# proto_base.net
KiCad netlist of a schematic drawn in EAGLE
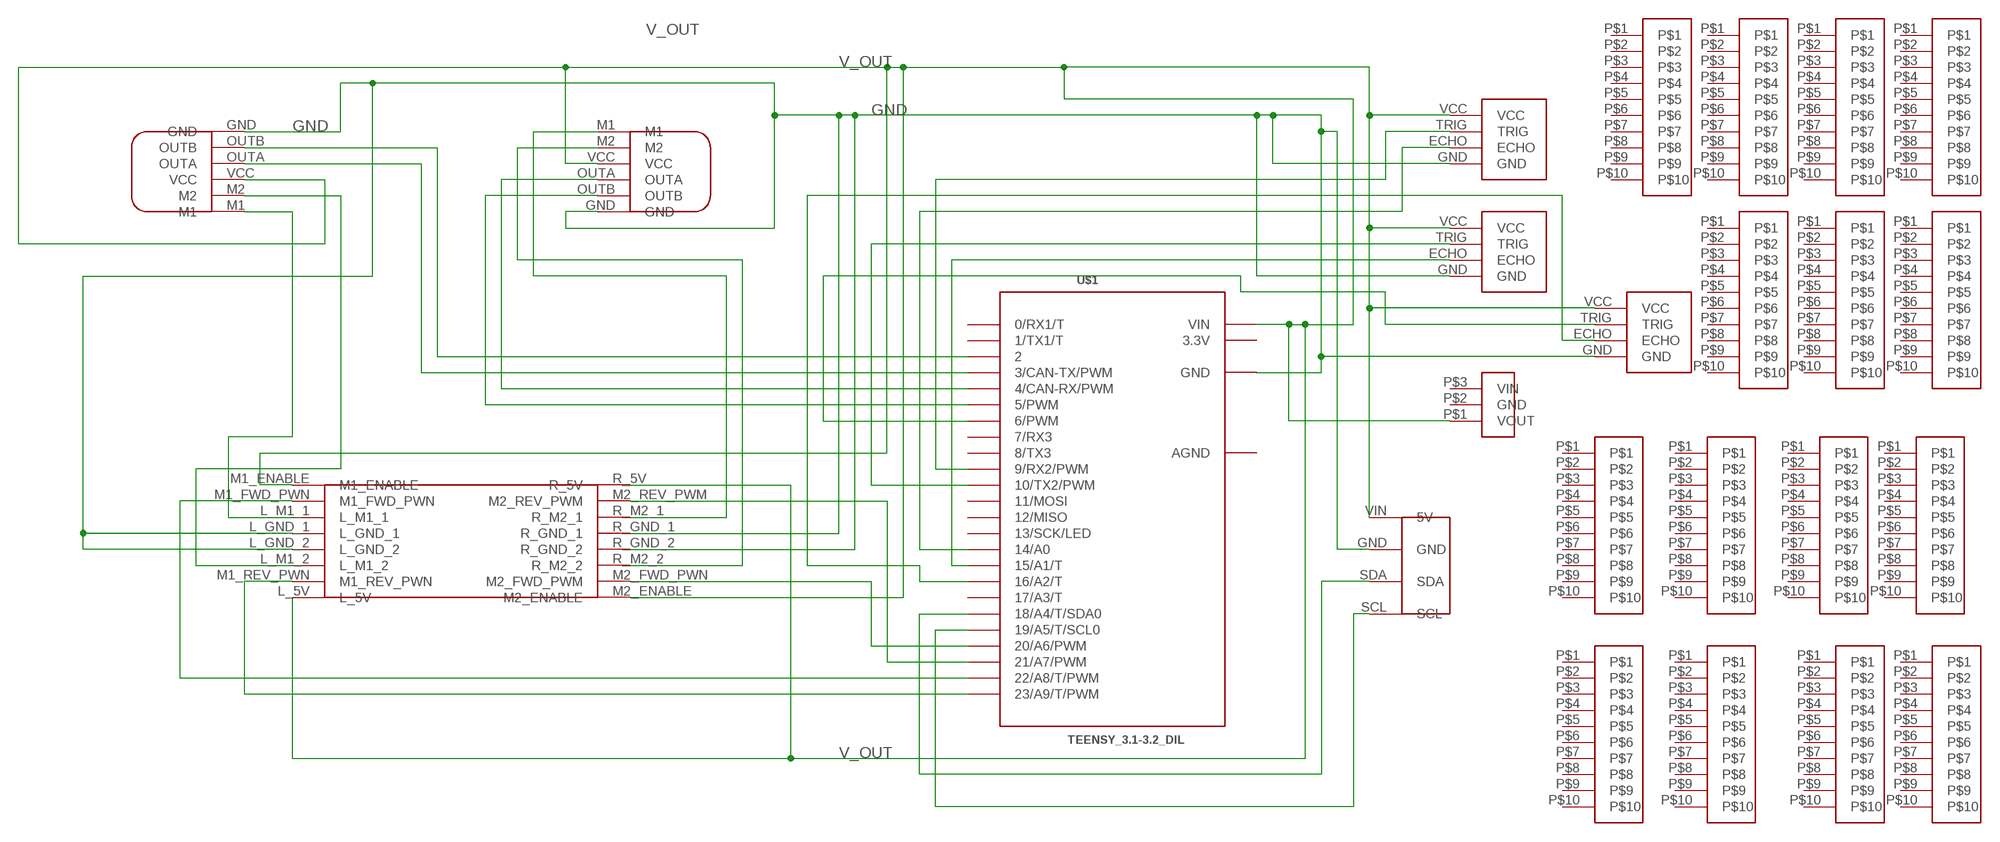
[diagram p0: schematic, sheet 1]

(export (version "E")
  (design (tool "Eeschema 10.0.6"))
  (components
    (comp (ref "IMU")
      (value "IMU")
      (footprint "eagle-import:IMU")
      (libsource (lib "eagle-import") (part "IMU"))
    )
    (comp (ref "LEFT_ENCODER")
      (value "MOTOR_ENCODER")
      (footprint "eagle-import:MOTOR_ENCODER")
      (libsource (lib "eagle-import") (part "MOTOR_ENCODER"))
    )
    (comp (ref "MOTOR_DRIVER")
      (value "MOTOR_DRIVER")
      (footprint "eagle-import:MOTOR_DRIVER")
      (libsource (lib "eagle-import") (part "MOTOR_DRIVER"))
    )
    (comp (ref "RIGHT_ENCODER")
      (value "MOTOR_ENCODER")
      (footprint "eagle-import:MOTOR_ENCODER")
      (libsource (lib "eagle-import") (part "MOTOR_ENCODER"))
    )
    (comp (ref "U$1")
      (value "TEENSY_3.1-3.2_DIL")
      (footprint "eagle-import:TEENSY_3.0-3.2&LC_DIL")
      (libsource (lib "eagle-import") (part "TEENSY_3.1-3.2_DIL"))
    )
    (comp (ref "U$2")
      (value "VOLTAGE_REGULATOR")
      (footprint "eagle-import:VOLTAGE_REGULATOR")
      (libsource (lib "eagle-import") (part "VOLTAGE_REGULATOR"))
    )
    (comp (ref "U$3")
      (value "SONAR_SENSOR")
      (footprint "eagle-import:SONAR_SENSOR")
      (libsource (lib "eagle-import") (part "SONAR_SENSOR"))
    )
    (comp (ref "U$4")
      (value "SONAR_SENSOR")
      (footprint "eagle-import:SONAR_SENSOR")
      (libsource (lib "eagle-import") (part "SONAR_SENSOR"))
    )
    (comp (ref "U$5")
      (value "SONAR_SENSOR")
      (footprint "eagle-import:SONAR_SENSOR")
      (libsource (lib "eagle-import") (part "SONAR_SENSOR"))
    )
    (comp (ref "U$6")
      (value "TEST_ROW")
      (footprint "eagle-import:TEST_ROW")
      (libsource (lib "eagle-import") (part "TEST_ROW"))
    )
    (comp (ref "U$7")
      (value "TEST_ROW")
      (footprint "eagle-import:TEST_ROW")
      (libsource (lib "eagle-import") (part "TEST_ROW"))
    )
    (comp (ref "U$8")
      (value "TEST_ROW")
      (footprint "eagle-import:TEST_ROW")
      (libsource (lib "eagle-import") (part "TEST_ROW"))
    )
    (comp (ref "U$9")
      (value "TEST_ROW")
      (footprint "eagle-import:TEST_ROW")
      (libsource (lib "eagle-import") (part "TEST_ROW"))
    )
    (comp (ref "U$10")
      (value "TEST_ROW")
      (footprint "eagle-import:TEST_ROW")
      (libsource (lib "eagle-import") (part "TEST_ROW"))
    )
    (comp (ref "U$11")
      (value "TEST_ROW")
      (footprint "eagle-import:TEST_ROW")
      (libsource (lib "eagle-import") (part "TEST_ROW"))
    )
    (comp (ref "U$12")
      (value "TEST_ROW")
      (footprint "eagle-import:TEST_ROW")
      (libsource (lib "eagle-import") (part "TEST_ROW"))
    )
    (comp (ref "U$13")
      (value "TEST_ROW")
      (footprint "eagle-import:TEST_ROW")
      (libsource (lib "eagle-import") (part "TEST_ROW"))
    )
    (comp (ref "U$14")
      (value "TEST_ROW")
      (footprint "eagle-import:TEST_ROW")
      (libsource (lib "eagle-import") (part "TEST_ROW"))
    )
    (comp (ref "U$15")
      (value "TEST_ROW")
      (footprint "eagle-import:TEST_ROW")
      (libsource (lib "eagle-import") (part "TEST_ROW"))
    )
    (comp (ref "U$16")
      (value "TEST_ROW")
      (footprint "eagle-import:TEST_ROW")
      (libsource (lib "eagle-import") (part "TEST_ROW"))
    )
    (comp (ref "U$17")
      (value "TEST_ROW")
      (footprint "eagle-import:TEST_ROW")
      (libsource (lib "eagle-import") (part "TEST_ROW"))
    )
    (comp (ref "U$18")
      (value "TEST_ROW")
      (footprint "eagle-import:TEST_ROW")
      (libsource (lib "eagle-import") (part "TEST_ROW"))
    )
    (comp (ref "U$19")
      (value "TEST_ROW")
      (footprint "eagle-import:TEST_ROW")
      (libsource (lib "eagle-import") (part "TEST_ROW"))
    )
    (comp (ref "U$20")
      (value "TEST_ROW")
      (footprint "eagle-import:TEST_ROW")
      (libsource (lib "eagle-import") (part "TEST_ROW"))
    )
  )
  (nets
    (net (code "1") (name "/3.3V") (class "Default")
      (node (ref "U$1") (pin "3.3V") (pinfunction "3.3V_3.3V") (pintype "power_in"))
    )
    (net (code "2") (name "/AGND") (class "Default")
      (node (ref "U$1") (pin "AGND") (pinfunction "AGND_AGND") (pintype "power_in"))
    )
    (net (code "3") (name "/GND") (class "Default")
      (node (ref "IMU") (pin "GND") (pinfunction "GND_GND") (pintype "bidirectional"))
      (node (ref "LEFT_ENCODER") (pin "GND") (pinfunction "GND_GND") (pintype "bidirectional"))
      (node (ref "MOTOR_DRIVER") (pin "L_GND_1") (pinfunction "L_GND_1_L_GND_1") (pintype "bidirectional"))
      (node (ref "MOTOR_DRIVER") (pin "L_GND_2") (pinfunction "L_GND_2_L_GND_2") (pintype "bidirectional"))
      (node (ref "MOTOR_DRIVER") (pin "R_GND_1") (pinfunction "R_GND_1_R_GND_1") (pintype "bidirectional"))
      (node (ref "MOTOR_DRIVER") (pin "R_GND_2") (pinfunction "R_GND_2_R_GND_2") (pintype "bidirectional"))
      (node (ref "RIGHT_ENCODER") (pin "GND") (pinfunction "GND_GND") (pintype "bidirectional"))
      (node (ref "U$1") (pin "GND") (pinfunction "GND_GND") (pintype "power_in"))
      (node (ref "U$3") (pin "GND") (pinfunction "GND_GND") (pintype "bidirectional"))
      (node (ref "U$4") (pin "GND") (pinfunction "GND_GND") (pintype "bidirectional"))
      (node (ref "U$5") (pin "GND") (pinfunction "GND_GND") (pintype "bidirectional"))
    )
    (net (code "4") (name "/V_OUT") (class "Default")
      (node (ref "IMU") (pin "VIN") (pinfunction "5V_VIN") (pintype "bidirectional"))
      (node (ref "LEFT_ENCODER") (pin "VCC") (pinfunction "VCC_VCC") (pintype "bidirectional"))
      (node (ref "MOTOR_DRIVER") (pin "L_5V") (pinfunction "L_5V_L_5V") (pintype "bidirectional"))
      (node (ref "MOTOR_DRIVER") (pin "M1_ENABLE") (pinfunction "M1_ENABLE_M1_ENABLE") (pintype "bidirectional"))
      (node (ref "MOTOR_DRIVER") (pin "M2_ENABLE") (pinfunction "M2_ENABLE_M2_ENABLE") (pintype "bidirectional"))
      (node (ref "MOTOR_DRIVER") (pin "R_5V") (pinfunction "R_5V_R_5V") (pintype "bidirectional"))
      (node (ref "RIGHT_ENCODER") (pin "VCC") (pinfunction "VCC_VCC") (pintype "bidirectional"))
      (node (ref "U$1") (pin "VIN") (pinfunction "VIN_VIN") (pintype "power_in"))
      (node (ref "U$2") (pin "P$1") (pinfunction "VOUT_P$1") (pintype "bidirectional"))
      (node (ref "U$3") (pin "VCC") (pinfunction "VCC_VCC") (pintype "bidirectional"))
      (node (ref "U$4") (pin "VCC") (pinfunction "VCC_VCC") (pintype "bidirectional"))
      (node (ref "U$5") (pin "VCC") (pinfunction "VCC_VCC") (pintype "bidirectional"))
    )
    (net (code "5") (name "Net-(LEFT_ENCODER-PadM1)") (class "Default")
      (node (ref "LEFT_ENCODER") (pin "M1") (pinfunction "M1_M1") (pintype "bidirectional"))
      (node (ref "MOTOR_DRIVER") (pin "L_M1_1") (pinfunction "L_M1_1_L_M1_1") (pintype "bidirectional"))
    )
    (net (code "6") (name "Net-(LEFT_ENCODER-PadM2)") (class "Default")
      (node (ref "LEFT_ENCODER") (pin "M2") (pinfunction "M2_M2") (pintype "bidirectional"))
      (node (ref "MOTOR_DRIVER") (pin "L_M1_2") (pinfunction "L_M1_2_L_M1_2") (pintype "bidirectional"))
    )
    (net (code "7") (name "Net-(LEFT_ENCODER-PadOUTB)") (class "Default")
      (node (ref "LEFT_ENCODER") (pin "OUTB") (pinfunction "OUTB_OUTB") (pintype "bidirectional"))
      (node (ref "U$1") (pin "2") (pinfunction "2_2") (pintype "bidirectional"))
    )
    (net (code "8") (name "Net-(MOTOR_DRIVER-M2_FWD_PWM)") (class "Default")
      (node (ref "MOTOR_DRIVER") (pin "M2_FWD_PWN") (pinfunction "M2_FWD_PWM_M2_FWD_PWN") (pintype "bidirectional"))
      (node (ref "U$1") (pin "20/A6") (pinfunction "20/A6/PWM_20/A6") (pintype "bidirectional"))
    )
    (net (code "9") (name "Net-(MOTOR_DRIVER-PadR_M2_1)") (class "Default")
      (node (ref "MOTOR_DRIVER") (pin "R_M2_1") (pinfunction "R_M2_1_R_M2_1") (pintype "bidirectional"))
      (node (ref "RIGHT_ENCODER") (pin "M1") (pinfunction "M1_M1") (pintype "bidirectional"))
    )
    (net (code "10") (name "Net-(MOTOR_DRIVER-PadR_M2_2)") (class "Default")
      (node (ref "MOTOR_DRIVER") (pin "R_M2_2") (pinfunction "R_M2_2_R_M2_2") (pintype "bidirectional"))
      (node (ref "RIGHT_ENCODER") (pin "M2") (pinfunction "M2_M2") (pintype "bidirectional"))
    )
    (net (code "11") (name "Net-(U$1-3{slash}CAN-TX{slash}PWM)") (class "Default")
      (node (ref "LEFT_ENCODER") (pin "OUTA") (pinfunction "OUTA_OUTA") (pintype "bidirectional"))
      (node (ref "U$1") (pin "3") (pinfunction "3/CAN-TX/PWM_3") (pintype "bidirectional"))
    )
    (net (code "12") (name "Net-(U$1-4{slash}CAN-RX{slash}PWM)") (class "Default")
      (node (ref "RIGHT_ENCODER") (pin "OUTA") (pinfunction "OUTA_OUTA") (pintype "bidirectional"))
      (node (ref "U$1") (pin "4") (pinfunction "4/CAN-RX/PWM_4") (pintype "bidirectional"))
    )
    (net (code "13") (name "Net-(U$1-5{slash}PWM)") (class "Default")
      (node (ref "RIGHT_ENCODER") (pin "OUTB") (pinfunction "OUTB_OUTB") (pintype "bidirectional"))
      (node (ref "U$1") (pin "5") (pinfunction "5/PWM_5") (pintype "bidirectional"))
    )
    (net (code "14") (name "Net-(U$1-6{slash}PWM)") (class "Default")
      (node (ref "U$1") (pin "6") (pinfunction "6/PWM_6") (pintype "bidirectional"))
      (node (ref "U$5") (pin "TRIG") (pinfunction "TRIG_TRIG") (pintype "bidirectional"))
    )
    (net (code "15") (name "Net-(U$1-9{slash}RX2{slash}PWM)") (class "Default")
      (node (ref "U$1") (pin "9") (pinfunction "9/RX2/PWM_9") (pintype "bidirectional"))
      (node (ref "U$3") (pin "TRIG") (pinfunction "TRIG_TRIG") (pintype "bidirectional"))
    )
    (net (code "16") (name "Net-(U$1-10{slash}TX2{slash}PWM)") (class "Default")
      (node (ref "U$1") (pin "10") (pinfunction "10/TX2/PWM_10") (pintype "bidirectional"))
      (node (ref "U$4") (pin "TRIG") (pinfunction "TRIG_TRIG") (pintype "bidirectional"))
    )
    (net (code "17") (name "Net-(U$1-15{slash}A1{slash}T)") (class "Default")
      (node (ref "U$1") (pin "15/A1") (pinfunction "15/A1/T_15/A1") (pintype "bidirectional"))
      (node (ref "U$4") (pin "ECHO") (pinfunction "ECHO_ECHO") (pintype "bidirectional"))
    )
    (net (code "18") (name "Net-(U$1-16{slash}A2{slash}T)") (class "Default")
      (node (ref "U$1") (pin "16/A2") (pinfunction "16/A2/T_16/A2") (pintype "bidirectional"))
      (node (ref "U$5") (pin "ECHO") (pinfunction "ECHO_ECHO") (pintype "bidirectional"))
    )
    (net (code "19") (name "Net-(U$1-18{slash}A4{slash}T{slash}SDA0)") (class "Default")
      (node (ref "IMU") (pin "SDA") (pinfunction "SDA_SDA") (pintype "bidirectional"))
      (node (ref "U$1") (pin "18/A4") (pinfunction "18/A4/T/SDA0_18/A4") (pintype "bidirectional"))
    )
    (net (code "20") (name "Net-(U$1-19{slash}A5{slash}T{slash}SCL0)") (class "Default")
      (node (ref "IMU") (pin "SCL") (pinfunction "SCL_SCL") (pintype "bidirectional"))
      (node (ref "U$1") (pin "19/A5") (pinfunction "19/A5/T/SCL0_19/A5") (pintype "bidirectional"))
    )
    (net (code "21") (name "Net-(U$1-21{slash}A7{slash}PWM)") (class "Default")
      (node (ref "MOTOR_DRIVER") (pin "M2_REV_PWM") (pinfunction "M2_REV_PWM_M2_REV_PWM") (pintype "bidirectional"))
      (node (ref "U$1") (pin "21/A7") (pinfunction "21/A7/PWM_21/A7") (pintype "bidirectional"))
    )
    (net (code "22") (name "Net-(U$1-22{slash}A8{slash}T{slash}PWM)") (class "Default")
      (node (ref "MOTOR_DRIVER") (pin "M1_FWD_PWN") (pinfunction "M1_FWD_PWN_M1_FWD_PWN") (pintype "bidirectional"))
      (node (ref "U$1") (pin "22/A8") (pinfunction "22/A8/T/PWM_22/A8") (pintype "bidirectional"))
    )
    (net (code "23") (name "Net-(U$1-23{slash}A9{slash}T{slash}PWM)") (class "Default")
      (node (ref "MOTOR_DRIVER") (pin "M1_REV_PWN") (pinfunction "M1_REV_PWN_M1_REV_PWN") (pintype "bidirectional"))
      (node (ref "U$1") (pin "23/A9") (pinfunction "23/A9/T/PWM_23/A9") (pintype "bidirectional"))
    )
    (net (code "24") (name "Net-(U$1-Pad14{slash}A0)") (class "Default")
      (node (ref "U$1") (pin "14/A0") (pinfunction "14/A0_14/A0") (pintype "bidirectional"))
      (node (ref "U$3") (pin "ECHO") (pinfunction "ECHO_ECHO") (pintype "bidirectional"))
    )
    (net (code "25") (name "unconnected-(U$1-0{slash}RX1{slash}T-Pad0)") (class "Default")
      (node (ref "U$1") (pin "0") (pinfunction "0/RX1/T_0") (pintype "bidirectional"))
    )
    (net (code "26") (name "unconnected-(U$1-1{slash}TX1{slash}T-Pad1)") (class "Default")
      (node (ref "U$1") (pin "1") (pinfunction "1/TX1/T_1") (pintype "bidirectional"))
    )
    (net (code "27") (name "unconnected-(U$1-7{slash}RX3-Pad7)") (class "Default")
      (node (ref "U$1") (pin "7") (pinfunction "7/RX3_7") (pintype "bidirectional"))
    )
    (net (code "28") (name "unconnected-(U$1-8{slash}TX3-Pad8)") (class "Default")
      (node (ref "U$1") (pin "8") (pinfunction "8/TX3_8") (pintype "bidirectional"))
    )
    (net (code "29") (name "unconnected-(U$1-11{slash}MOSI-Pad11)") (class "Default")
      (node (ref "U$1") (pin "11") (pinfunction "11/MOSI_11") (pintype "bidirectional"))
    )
    (net (code "30") (name "unconnected-(U$1-12{slash}MISO-Pad12)") (class "Default")
      (node (ref "U$1") (pin "12") (pinfunction "12/MISO_12") (pintype "bidirectional"))
    )
    (net (code "31") (name "unconnected-(U$1-13{slash}SCK{slash}LED-Pad13)") (class "Default")
      (node (ref "U$1") (pin "13") (pinfunction "13/SCK/LED_13") (pintype "bidirectional"))
    )
    (net (code "32") (name "unconnected-(U$1-17{slash}A3{slash}T-Pad17{slash}A3)") (class "Default")
      (node (ref "U$1") (pin "17/A3") (pinfunction "17/A3/T_17/A3") (pintype "bidirectional"))
    )
    (net (code "33") (name "unconnected-(U$2-GND-PadP$2)") (class "Default")
      (node (ref "U$2") (pin "P$2") (pinfunction "GND_P$2") (pintype "bidirectional"))
    )
    (net (code "34") (name "unconnected-(U$2-VIN-PadP$3)") (class "Default")
      (node (ref "U$2") (pin "P$3") (pinfunction "VIN_P$3") (pintype "bidirectional"))
    )
    (net (code "35") (name "unconnected-(U$6-PadP$1)") (class "Default")
      (node (ref "U$6") (pin "P$1") (pinfunction "P$1_P$1") (pintype "bidirectional"))
    )
    (net (code "36") (name "unconnected-(U$6-PadP$2)") (class "Default")
      (node (ref "U$6") (pin "P$2") (pinfunction "P$2_P$2") (pintype "bidirectional"))
    )
    (net (code "37") (name "unconnected-(U$6-PadP$3)") (class "Default")
      (node (ref "U$6") (pin "P$3") (pinfunction "P$3_P$3") (pintype "bidirectional"))
    )
    (net (code "38") (name "unconnected-(U$6-PadP$4)") (class "Default")
      (node (ref "U$6") (pin "P$4") (pinfunction "P$4_P$4") (pintype "bidirectional"))
    )
    (net (code "39") (name "unconnected-(U$6-PadP$5)") (class "Default")
      (node (ref "U$6") (pin "P$5") (pinfunction "P$5_P$5") (pintype "bidirectional"))
    )
    (net (code "40") (name "unconnected-(U$6-PadP$6)") (class "Default")
      (node (ref "U$6") (pin "P$6") (pinfunction "P$6_P$6") (pintype "bidirectional"))
    )
    (net (code "41") (name "unconnected-(U$6-PadP$7)") (class "Default")
      (node (ref "U$6") (pin "P$7") (pinfunction "P$7_P$7") (pintype "bidirectional"))
    )
    (net (code "42") (name "unconnected-(U$6-PadP$8)") (class "Default")
      (node (ref "U$6") (pin "P$8") (pinfunction "P$8_P$8") (pintype "bidirectional"))
    )
    (net (code "43") (name "unconnected-(U$6-PadP$9)") (class "Default")
      (node (ref "U$6") (pin "P$9") (pinfunction "P$9_P$9") (pintype "bidirectional"))
    )
    (net (code "44") (name "unconnected-(U$6-PadP$10)") (class "Default")
      (node (ref "U$6") (pin "P$10") (pinfunction "P$10_P$10") (pintype "bidirectional"))
    )
    (net (code "45") (name "unconnected-(U$7-PadP$1)") (class "Default")
      (node (ref "U$7") (pin "P$1") (pinfunction "P$1_P$1") (pintype "bidirectional"))
    )
    (net (code "46") (name "unconnected-(U$7-PadP$2)") (class "Default")
      (node (ref "U$7") (pin "P$2") (pinfunction "P$2_P$2") (pintype "bidirectional"))
    )
    (net (code "47") (name "unconnected-(U$7-PadP$3)") (class "Default")
      (node (ref "U$7") (pin "P$3") (pinfunction "P$3_P$3") (pintype "bidirectional"))
    )
    (net (code "48") (name "unconnected-(U$7-PadP$4)") (class "Default")
      (node (ref "U$7") (pin "P$4") (pinfunction "P$4_P$4") (pintype "bidirectional"))
    )
    (net (code "49") (name "unconnected-(U$7-PadP$5)") (class "Default")
      (node (ref "U$7") (pin "P$5") (pinfunction "P$5_P$5") (pintype "bidirectional"))
    )
    (net (code "50") (name "unconnected-(U$7-PadP$6)") (class "Default")
      (node (ref "U$7") (pin "P$6") (pinfunction "P$6_P$6") (pintype "bidirectional"))
    )
    (net (code "51") (name "unconnected-(U$7-PadP$7)") (class "Default")
      (node (ref "U$7") (pin "P$7") (pinfunction "P$7_P$7") (pintype "bidirectional"))
    )
    (net (code "52") (name "unconnected-(U$7-PadP$8)") (class "Default")
      (node (ref "U$7") (pin "P$8") (pinfunction "P$8_P$8") (pintype "bidirectional"))
    )
    (net (code "53") (name "unconnected-(U$7-PadP$9)") (class "Default")
      (node (ref "U$7") (pin "P$9") (pinfunction "P$9_P$9") (pintype "bidirectional"))
    )
    (net (code "54") (name "unconnected-(U$7-PadP$10)") (class "Default")
      (node (ref "U$7") (pin "P$10") (pinfunction "P$10_P$10") (pintype "bidirectional"))
    )
    (net (code "55") (name "unconnected-(U$8-PadP$1)") (class "Default")
      (node (ref "U$8") (pin "P$1") (pinfunction "P$1_P$1") (pintype "bidirectional"))
    )
    (net (code "56") (name "unconnected-(U$8-PadP$2)") (class "Default")
      (node (ref "U$8") (pin "P$2") (pinfunction "P$2_P$2") (pintype "bidirectional"))
    )
    (net (code "57") (name "unconnected-(U$8-PadP$3)") (class "Default")
      (node (ref "U$8") (pin "P$3") (pinfunction "P$3_P$3") (pintype "bidirectional"))
    )
    (net (code "58") (name "unconnected-(U$8-PadP$4)") (class "Default")
      (node (ref "U$8") (pin "P$4") (pinfunction "P$4_P$4") (pintype "bidirectional"))
    )
    (net (code "59") (name "unconnected-(U$8-PadP$5)") (class "Default")
      (node (ref "U$8") (pin "P$5") (pinfunction "P$5_P$5") (pintype "bidirectional"))
    )
    (net (code "60") (name "unconnected-(U$8-PadP$6)") (class "Default")
      (node (ref "U$8") (pin "P$6") (pinfunction "P$6_P$6") (pintype "bidirectional"))
    )
    (net (code "61") (name "unconnected-(U$8-PadP$7)") (class "Default")
      (node (ref "U$8") (pin "P$7") (pinfunction "P$7_P$7") (pintype "bidirectional"))
    )
    (net (code "62") (name "unconnected-(U$8-PadP$8)") (class "Default")
      (node (ref "U$8") (pin "P$8") (pinfunction "P$8_P$8") (pintype "bidirectional"))
    )
    (net (code "63") (name "unconnected-(U$8-PadP$9)") (class "Default")
      (node (ref "U$8") (pin "P$9") (pinfunction "P$9_P$9") (pintype "bidirectional"))
    )
    (net (code "64") (name "unconnected-(U$8-PadP$10)") (class "Default")
      (node (ref "U$8") (pin "P$10") (pinfunction "P$10_P$10") (pintype "bidirectional"))
    )
    (net (code "65") (name "unconnected-(U$9-PadP$1)") (class "Default")
      (node (ref "U$9") (pin "P$1") (pinfunction "P$1_P$1") (pintype "bidirectional"))
    )
    (net (code "66") (name "unconnected-(U$9-PadP$2)") (class "Default")
      (node (ref "U$9") (pin "P$2") (pinfunction "P$2_P$2") (pintype "bidirectional"))
    )
    (net (code "67") (name "unconnected-(U$9-PadP$3)") (class "Default")
      (node (ref "U$9") (pin "P$3") (pinfunction "P$3_P$3") (pintype "bidirectional"))
    )
    (net (code "68") (name "unconnected-(U$9-PadP$4)") (class "Default")
      (node (ref "U$9") (pin "P$4") (pinfunction "P$4_P$4") (pintype "bidirectional"))
    )
    (net (code "69") (name "unconnected-(U$9-PadP$5)") (class "Default")
      (node (ref "U$9") (pin "P$5") (pinfunction "P$5_P$5") (pintype "bidirectional"))
    )
    (net (code "70") (name "unconnected-(U$9-PadP$6)") (class "Default")
      (node (ref "U$9") (pin "P$6") (pinfunction "P$6_P$6") (pintype "bidirectional"))
    )
    (net (code "71") (name "unconnected-(U$9-PadP$7)") (class "Default")
      (node (ref "U$9") (pin "P$7") (pinfunction "P$7_P$7") (pintype "bidirectional"))
    )
    (net (code "72") (name "unconnected-(U$9-PadP$8)") (class "Default")
      (node (ref "U$9") (pin "P$8") (pinfunction "P$8_P$8") (pintype "bidirectional"))
    )
    (net (code "73") (name "unconnected-(U$9-PadP$9)") (class "Default")
      (node (ref "U$9") (pin "P$9") (pinfunction "P$9_P$9") (pintype "bidirectional"))
    )
    (net (code "74") (name "unconnected-(U$9-PadP$10)") (class "Default")
      (node (ref "U$9") (pin "P$10") (pinfunction "P$10_P$10") (pintype "bidirectional"))
    )
    (net (code "75") (name "unconnected-(U$10-PadP$1)") (class "Default")
      (node (ref "U$10") (pin "P$1") (pinfunction "P$1_P$1") (pintype "bidirectional"))
    )
    (net (code "76") (name "unconnected-(U$10-PadP$2)") (class "Default")
      (node (ref "U$10") (pin "P$2") (pinfunction "P$2_P$2") (pintype "bidirectional"))
    )
    (net (code "77") (name "unconnected-(U$10-PadP$3)") (class "Default")
      (node (ref "U$10") (pin "P$3") (pinfunction "P$3_P$3") (pintype "bidirectional"))
    )
    (net (code "78") (name "unconnected-(U$10-PadP$4)") (class "Default")
      (node (ref "U$10") (pin "P$4") (pinfunction "P$4_P$4") (pintype "bidirectional"))
    )
    (net (code "79") (name "unconnected-(U$10-PadP$5)") (class "Default")
      (node (ref "U$10") (pin "P$5") (pinfunction "P$5_P$5") (pintype "bidirectional"))
    )
    (net (code "80") (name "unconnected-(U$10-PadP$6)") (class "Default")
      (node (ref "U$10") (pin "P$6") (pinfunction "P$6_P$6") (pintype "bidirectional"))
    )
    (net (code "81") (name "unconnected-(U$10-PadP$7)") (class "Default")
      (node (ref "U$10") (pin "P$7") (pinfunction "P$7_P$7") (pintype "bidirectional"))
    )
    (net (code "82") (name "unconnected-(U$10-PadP$8)") (class "Default")
      (node (ref "U$10") (pin "P$8") (pinfunction "P$8_P$8") (pintype "bidirectional"))
    )
    (net (code "83") (name "unconnected-(U$10-PadP$9)") (class "Default")
      (node (ref "U$10") (pin "P$9") (pinfunction "P$9_P$9") (pintype "bidirectional"))
    )
    (net (code "84") (name "unconnected-(U$10-PadP$10)") (class "Default")
      (node (ref "U$10") (pin "P$10") (pinfunction "P$10_P$10") (pintype "bidirectional"))
    )
    (net (code "85") (name "unconnected-(U$11-PadP$1)") (class "Default")
      (node (ref "U$11") (pin "P$1") (pinfunction "P$1_P$1") (pintype "bidirectional"))
    )
    (net (code "86") (name "unconnected-(U$11-PadP$2)") (class "Default")
      (node (ref "U$11") (pin "P$2") (pinfunction "P$2_P$2") (pintype "bidirectional"))
    )
    (net (code "87") (name "unconnected-(U$11-PadP$3)") (class "Default")
      (node (ref "U$11") (pin "P$3") (pinfunction "P$3_P$3") (pintype "bidirectional"))
    )
    (net (code "88") (name "unconnected-(U$11-PadP$4)") (class "Default")
      (node (ref "U$11") (pin "P$4") (pinfunction "P$4_P$4") (pintype "bidirectional"))
    )
    (net (code "89") (name "unconnected-(U$11-PadP$5)") (class "Default")
      (node (ref "U$11") (pin "P$5") (pinfunction "P$5_P$5") (pintype "bidirectional"))
    )
    (net (code "90") (name "unconnected-(U$11-PadP$6)") (class "Default")
      (node (ref "U$11") (pin "P$6") (pinfunction "P$6_P$6") (pintype "bidirectional"))
    )
    (net (code "91") (name "unconnected-(U$11-PadP$7)") (class "Default")
      (node (ref "U$11") (pin "P$7") (pinfunction "P$7_P$7") (pintype "bidirectional"))
    )
    (net (code "92") (name "unconnected-(U$11-PadP$8)") (class "Default")
      (node (ref "U$11") (pin "P$8") (pinfunction "P$8_P$8") (pintype "bidirectional"))
    )
    (net (code "93") (name "unconnected-(U$11-PadP$9)") (class "Default")
      (node (ref "U$11") (pin "P$9") (pinfunction "P$9_P$9") (pintype "bidirectional"))
    )
    (net (code "94") (name "unconnected-(U$11-PadP$10)") (class "Default")
      (node (ref "U$11") (pin "P$10") (pinfunction "P$10_P$10") (pintype "bidirectional"))
    )
    (net (code "95") (name "unconnected-(U$12-PadP$1)") (class "Default")
      (node (ref "U$12") (pin "P$1") (pinfunction "P$1_P$1") (pintype "bidirectional"))
    )
    (net (code "96") (name "unconnected-(U$12-PadP$2)") (class "Default")
      (node (ref "U$12") (pin "P$2") (pinfunction "P$2_P$2") (pintype "bidirectional"))
    )
    (net (code "97") (name "unconnected-(U$12-PadP$3)") (class "Default")
      (node (ref "U$12") (pin "P$3") (pinfunction "P$3_P$3") (pintype "bidirectional"))
    )
    (net (code "98") (name "unconnected-(U$12-PadP$4)") (class "Default")
      (node (ref "U$12") (pin "P$4") (pinfunction "P$4_P$4") (pintype "bidirectional"))
    )
    (net (code "99") (name "unconnected-(U$12-PadP$5)") (class "Default")
      (node (ref "U$12") (pin "P$5") (pinfunction "P$5_P$5") (pintype "bidirectional"))
    )
    (net (code "100") (name "unconnected-(U$12-PadP$6)") (class "Default")
      (node (ref "U$12") (pin "P$6") (pinfunction "P$6_P$6") (pintype "bidirectional"))
    )
    (net (code "101") (name "unconnected-(U$12-PadP$7)") (class "Default")
      (node (ref "U$12") (pin "P$7") (pinfunction "P$7_P$7") (pintype "bidirectional"))
    )
    (net (code "102") (name "unconnected-(U$12-PadP$8)") (class "Default")
      (node (ref "U$12") (pin "P$8") (pinfunction "P$8_P$8") (pintype "bidirectional"))
    )
    (net (code "103") (name "unconnected-(U$12-PadP$9)") (class "Default")
      (node (ref "U$12") (pin "P$9") (pinfunction "P$9_P$9") (pintype "bidirectional"))
    )
    (net (code "104") (name "unconnected-(U$12-PadP$10)") (class "Default")
      (node (ref "U$12") (pin "P$10") (pinfunction "P$10_P$10") (pintype "bidirectional"))
    )
    (net (code "105") (name "unconnected-(U$13-PadP$1)") (class "Default")
      (node (ref "U$13") (pin "P$1") (pinfunction "P$1_P$1") (pintype "bidirectional"))
    )
    (net (code "106") (name "unconnected-(U$13-PadP$2)") (class "Default")
      (node (ref "U$13") (pin "P$2") (pinfunction "P$2_P$2") (pintype "bidirectional"))
    )
    (net (code "107") (name "unconnected-(U$13-PadP$3)") (class "Default")
      (node (ref "U$13") (pin "P$3") (pinfunction "P$3_P$3") (pintype "bidirectional"))
    )
    (net (code "108") (name "unconnected-(U$13-PadP$4)") (class "Default")
      (node (ref "U$13") (pin "P$4") (pinfunction "P$4_P$4") (pintype "bidirectional"))
    )
    (net (code "109") (name "unconnected-(U$13-PadP$5)") (class "Default")
      (node (ref "U$13") (pin "P$5") (pinfunction "P$5_P$5") (pintype "bidirectional"))
    )
    (net (code "110") (name "unconnected-(U$13-PadP$6)") (class "Default")
      (node (ref "U$13") (pin "P$6") (pinfunction "P$6_P$6") (pintype "bidirectional"))
    )
    (net (code "111") (name "unconnected-(U$13-PadP$7)") (class "Default")
      (node (ref "U$13") (pin "P$7") (pinfunction "P$7_P$7") (pintype "bidirectional"))
    )
    (net (code "112") (name "unconnected-(U$13-PadP$8)") (class "Default")
      (node (ref "U$13") (pin "P$8") (pinfunction "P$8_P$8") (pintype "bidirectional"))
    )
    (net (code "113") (name "unconnected-(U$13-PadP$9)") (class "Default")
      (node (ref "U$13") (pin "P$9") (pinfunction "P$9_P$9") (pintype "bidirectional"))
    )
    (net (code "114") (name "unconnected-(U$13-PadP$10)") (class "Default")
      (node (ref "U$13") (pin "P$10") (pinfunction "P$10_P$10") (pintype "bidirectional"))
    )
    (net (code "115") (name "unconnected-(U$14-PadP$1)") (class "Default")
      (node (ref "U$14") (pin "P$1") (pinfunction "P$1_P$1") (pintype "bidirectional"))
    )
    (net (code "116") (name "unconnected-(U$14-PadP$2)") (class "Default")
      (node (ref "U$14") (pin "P$2") (pinfunction "P$2_P$2") (pintype "bidirectional"))
    )
    (net (code "117") (name "unconnected-(U$14-PadP$3)") (class "Default")
      (node (ref "U$14") (pin "P$3") (pinfunction "P$3_P$3") (pintype "bidirectional"))
    )
    (net (code "118") (name "unconnected-(U$14-PadP$4)") (class "Default")
      (node (ref "U$14") (pin "P$4") (pinfunction "P$4_P$4") (pintype "bidirectional"))
    )
    (net (code "119") (name "unconnected-(U$14-PadP$5)") (class "Default")
      (node (ref "U$14") (pin "P$5") (pinfunction "P$5_P$5") (pintype "bidirectional"))
    )
    (net (code "120") (name "unconnected-(U$14-PadP$6)") (class "Default")
      (node (ref "U$14") (pin "P$6") (pinfunction "P$6_P$6") (pintype "bidirectional"))
    )
    (net (code "121") (name "unconnected-(U$14-PadP$7)") (class "Default")
      (node (ref "U$14") (pin "P$7") (pinfunction "P$7_P$7") (pintype "bidirectional"))
    )
    (net (code "122") (name "unconnected-(U$14-PadP$8)") (class "Default")
      (node (ref "U$14") (pin "P$8") (pinfunction "P$8_P$8") (pintype "bidirectional"))
    )
    (net (code "123") (name "unconnected-(U$14-PadP$9)") (class "Default")
      (node (ref "U$14") (pin "P$9") (pinfunction "P$9_P$9") (pintype "bidirectional"))
    )
    (net (code "124") (name "unconnected-(U$14-PadP$10)") (class "Default")
      (node (ref "U$14") (pin "P$10") (pinfunction "P$10_P$10") (pintype "bidirectional"))
    )
    (net (code "125") (name "unconnected-(U$15-PadP$1)") (class "Default")
      (node (ref "U$15") (pin "P$1") (pinfunction "P$1_P$1") (pintype "bidirectional"))
    )
    (net (code "126") (name "unconnected-(U$15-PadP$2)") (class "Default")
      (node (ref "U$15") (pin "P$2") (pinfunction "P$2_P$2") (pintype "bidirectional"))
    )
    (net (code "127") (name "unconnected-(U$15-PadP$3)") (class "Default")
      (node (ref "U$15") (pin "P$3") (pinfunction "P$3_P$3") (pintype "bidirectional"))
    )
    (net (code "128") (name "unconnected-(U$15-PadP$4)") (class "Default")
      (node (ref "U$15") (pin "P$4") (pinfunction "P$4_P$4") (pintype "bidirectional"))
    )
    (net (code "129") (name "unconnected-(U$15-PadP$5)") (class "Default")
      (node (ref "U$15") (pin "P$5") (pinfunction "P$5_P$5") (pintype "bidirectional"))
    )
    (net (code "130") (name "unconnected-(U$15-PadP$6)") (class "Default")
      (node (ref "U$15") (pin "P$6") (pinfunction "P$6_P$6") (pintype "bidirectional"))
    )
    (net (code "131") (name "unconnected-(U$15-PadP$7)") (class "Default")
      (node (ref "U$15") (pin "P$7") (pinfunction "P$7_P$7") (pintype "bidirectional"))
    )
    (net (code "132") (name "unconnected-(U$15-PadP$8)") (class "Default")
      (node (ref "U$15") (pin "P$8") (pinfunction "P$8_P$8") (pintype "bidirectional"))
    )
    (net (code "133") (name "unconnected-(U$15-PadP$9)") (class "Default")
      (node (ref "U$15") (pin "P$9") (pinfunction "P$9_P$9") (pintype "bidirectional"))
    )
    (net (code "134") (name "unconnected-(U$15-PadP$10)") (class "Default")
      (node (ref "U$15") (pin "P$10") (pinfunction "P$10_P$10") (pintype "bidirectional"))
    )
    (net (code "135") (name "unconnected-(U$16-PadP$1)") (class "Default")
      (node (ref "U$16") (pin "P$1") (pinfunction "P$1_P$1") (pintype "bidirectional"))
    )
    (net (code "136") (name "unconnected-(U$16-PadP$2)") (class "Default")
      (node (ref "U$16") (pin "P$2") (pinfunction "P$2_P$2") (pintype "bidirectional"))
    )
    (net (code "137") (name "unconnected-(U$16-PadP$3)") (class "Default")
      (node (ref "U$16") (pin "P$3") (pinfunction "P$3_P$3") (pintype "bidirectional"))
    )
    (net (code "138") (name "unconnected-(U$16-PadP$4)") (class "Default")
      (node (ref "U$16") (pin "P$4") (pinfunction "P$4_P$4") (pintype "bidirectional"))
    )
    (net (code "139") (name "unconnected-(U$16-PadP$5)") (class "Default")
      (node (ref "U$16") (pin "P$5") (pinfunction "P$5_P$5") (pintype "bidirectional"))
    )
    (net (code "140") (name "unconnected-(U$16-PadP$6)") (class "Default")
      (node (ref "U$16") (pin "P$6") (pinfunction "P$6_P$6") (pintype "bidirectional"))
    )
    (net (code "141") (name "unconnected-(U$16-PadP$7)") (class "Default")
      (node (ref "U$16") (pin "P$7") (pinfunction "P$7_P$7") (pintype "bidirectional"))
    )
    (net (code "142") (name "unconnected-(U$16-PadP$8)") (class "Default")
      (node (ref "U$16") (pin "P$8") (pinfunction "P$8_P$8") (pintype "bidirectional"))
    )
    (net (code "143") (name "unconnected-(U$16-PadP$9)") (class "Default")
      (node (ref "U$16") (pin "P$9") (pinfunction "P$9_P$9") (pintype "bidirectional"))
    )
    (net (code "144") (name "unconnected-(U$16-PadP$10)") (class "Default")
      (node (ref "U$16") (pin "P$10") (pinfunction "P$10_P$10") (pintype "bidirectional"))
    )
    (net (code "145") (name "unconnected-(U$17-PadP$1)") (class "Default")
      (node (ref "U$17") (pin "P$1") (pinfunction "P$1_P$1") (pintype "bidirectional"))
    )
    (net (code "146") (name "unconnected-(U$17-PadP$2)") (class "Default")
      (node (ref "U$17") (pin "P$2") (pinfunction "P$2_P$2") (pintype "bidirectional"))
    )
    (net (code "147") (name "unconnected-(U$17-PadP$3)") (class "Default")
      (node (ref "U$17") (pin "P$3") (pinfunction "P$3_P$3") (pintype "bidirectional"))
    )
    (net (code "148") (name "unconnected-(U$17-PadP$4)") (class "Default")
      (node (ref "U$17") (pin "P$4") (pinfunction "P$4_P$4") (pintype "bidirectional"))
    )
    (net (code "149") (name "unconnected-(U$17-PadP$5)") (class "Default")
      (node (ref "U$17") (pin "P$5") (pinfunction "P$5_P$5") (pintype "bidirectional"))
    )
    (net (code "150") (name "unconnected-(U$17-PadP$6)") (class "Default")
      (node (ref "U$17") (pin "P$6") (pinfunction "P$6_P$6") (pintype "bidirectional"))
    )
    (net (code "151") (name "unconnected-(U$17-PadP$7)") (class "Default")
      (node (ref "U$17") (pin "P$7") (pinfunction "P$7_P$7") (pintype "bidirectional"))
    )
    (net (code "152") (name "unconnected-(U$17-PadP$8)") (class "Default")
      (node (ref "U$17") (pin "P$8") (pinfunction "P$8_P$8") (pintype "bidirectional"))
    )
    (net (code "153") (name "unconnected-(U$17-PadP$9)") (class "Default")
      (node (ref "U$17") (pin "P$9") (pinfunction "P$9_P$9") (pintype "bidirectional"))
    )
    (net (code "154") (name "unconnected-(U$17-PadP$10)") (class "Default")
      (node (ref "U$17") (pin "P$10") (pinfunction "P$10_P$10") (pintype "bidirectional"))
    )
    (net (code "155") (name "unconnected-(U$18-PadP$1)") (class "Default")
      (node (ref "U$18") (pin "P$1") (pinfunction "P$1_P$1") (pintype "bidirectional"))
    )
    (net (code "156") (name "unconnected-(U$18-PadP$2)") (class "Default")
      (node (ref "U$18") (pin "P$2") (pinfunction "P$2_P$2") (pintype "bidirectional"))
    )
    (net (code "157") (name "unconnected-(U$18-PadP$3)") (class "Default")
      (node (ref "U$18") (pin "P$3") (pinfunction "P$3_P$3") (pintype "bidirectional"))
    )
    (net (code "158") (name "unconnected-(U$18-PadP$4)") (class "Default")
      (node (ref "U$18") (pin "P$4") (pinfunction "P$4_P$4") (pintype "bidirectional"))
    )
    (net (code "159") (name "unconnected-(U$18-PadP$5)") (class "Default")
      (node (ref "U$18") (pin "P$5") (pinfunction "P$5_P$5") (pintype "bidirectional"))
    )
    (net (code "160") (name "unconnected-(U$18-PadP$6)") (class "Default")
      (node (ref "U$18") (pin "P$6") (pinfunction "P$6_P$6") (pintype "bidirectional"))
    )
    (net (code "161") (name "unconnected-(U$18-PadP$7)") (class "Default")
      (node (ref "U$18") (pin "P$7") (pinfunction "P$7_P$7") (pintype "bidirectional"))
    )
    (net (code "162") (name "unconnected-(U$18-PadP$8)") (class "Default")
      (node (ref "U$18") (pin "P$8") (pinfunction "P$8_P$8") (pintype "bidirectional"))
    )
    (net (code "163") (name "unconnected-(U$18-PadP$9)") (class "Default")
      (node (ref "U$18") (pin "P$9") (pinfunction "P$9_P$9") (pintype "bidirectional"))
    )
    (net (code "164") (name "unconnected-(U$18-PadP$10)") (class "Default")
      (node (ref "U$18") (pin "P$10") (pinfunction "P$10_P$10") (pintype "bidirectional"))
    )
    (net (code "165") (name "unconnected-(U$19-PadP$1)") (class "Default")
      (node (ref "U$19") (pin "P$1") (pinfunction "P$1_P$1") (pintype "bidirectional"))
    )
    (net (code "166") (name "unconnected-(U$19-PadP$2)") (class "Default")
      (node (ref "U$19") (pin "P$2") (pinfunction "P$2_P$2") (pintype "bidirectional"))
    )
    (net (code "167") (name "unconnected-(U$19-PadP$3)") (class "Default")
      (node (ref "U$19") (pin "P$3") (pinfunction "P$3_P$3") (pintype "bidirectional"))
    )
    (net (code "168") (name "unconnected-(U$19-PadP$4)") (class "Default")
      (node (ref "U$19") (pin "P$4") (pinfunction "P$4_P$4") (pintype "bidirectional"))
    )
    (net (code "169") (name "unconnected-(U$19-PadP$5)") (class "Default")
      (node (ref "U$19") (pin "P$5") (pinfunction "P$5_P$5") (pintype "bidirectional"))
    )
    (net (code "170") (name "unconnected-(U$19-PadP$6)") (class "Default")
      (node (ref "U$19") (pin "P$6") (pinfunction "P$6_P$6") (pintype "bidirectional"))
    )
    (net (code "171") (name "unconnected-(U$19-PadP$7)") (class "Default")
      (node (ref "U$19") (pin "P$7") (pinfunction "P$7_P$7") (pintype "bidirectional"))
    )
    (net (code "172") (name "unconnected-(U$19-PadP$8)") (class "Default")
      (node (ref "U$19") (pin "P$8") (pinfunction "P$8_P$8") (pintype "bidirectional"))
    )
    (net (code "173") (name "unconnected-(U$19-PadP$9)") (class "Default")
      (node (ref "U$19") (pin "P$9") (pinfunction "P$9_P$9") (pintype "bidirectional"))
    )
    (net (code "174") (name "unconnected-(U$19-PadP$10)") (class "Default")
      (node (ref "U$19") (pin "P$10") (pinfunction "P$10_P$10") (pintype "bidirectional"))
    )
    (net (code "175") (name "unconnected-(U$20-PadP$1)") (class "Default")
      (node (ref "U$20") (pin "P$1") (pinfunction "P$1_P$1") (pintype "bidirectional"))
    )
    (net (code "176") (name "unconnected-(U$20-PadP$2)") (class "Default")
      (node (ref "U$20") (pin "P$2") (pinfunction "P$2_P$2") (pintype "bidirectional"))
    )
    (net (code "177") (name "unconnected-(U$20-PadP$3)") (class "Default")
      (node (ref "U$20") (pin "P$3") (pinfunction "P$3_P$3") (pintype "bidirectional"))
    )
    (net (code "178") (name "unconnected-(U$20-PadP$4)") (class "Default")
      (node (ref "U$20") (pin "P$4") (pinfunction "P$4_P$4") (pintype "bidirectional"))
    )
    (net (code "179") (name "unconnected-(U$20-PadP$5)") (class "Default")
      (node (ref "U$20") (pin "P$5") (pinfunction "P$5_P$5") (pintype "bidirectional"))
    )
    (net (code "180") (name "unconnected-(U$20-PadP$6)") (class "Default")
      (node (ref "U$20") (pin "P$6") (pinfunction "P$6_P$6") (pintype "bidirectional"))
    )
    (net (code "181") (name "unconnected-(U$20-PadP$7)") (class "Default")
      (node (ref "U$20") (pin "P$7") (pinfunction "P$7_P$7") (pintype "bidirectional"))
    )
    (net (code "182") (name "unconnected-(U$20-PadP$8)") (class "Default")
      (node (ref "U$20") (pin "P$8") (pinfunction "P$8_P$8") (pintype "bidirectional"))
    )
    (net (code "183") (name "unconnected-(U$20-PadP$9)") (class "Default")
      (node (ref "U$20") (pin "P$9") (pinfunction "P$9_P$9") (pintype "bidirectional"))
    )
    (net (code "184") (name "unconnected-(U$20-PadP$10)") (class "Default")
      (node (ref "U$20") (pin "P$10") (pinfunction "P$10_P$10") (pintype "bidirectional"))
    )
  )
)
